# drv4.net
KiCad netlist of a schematic drawn in EAGLE
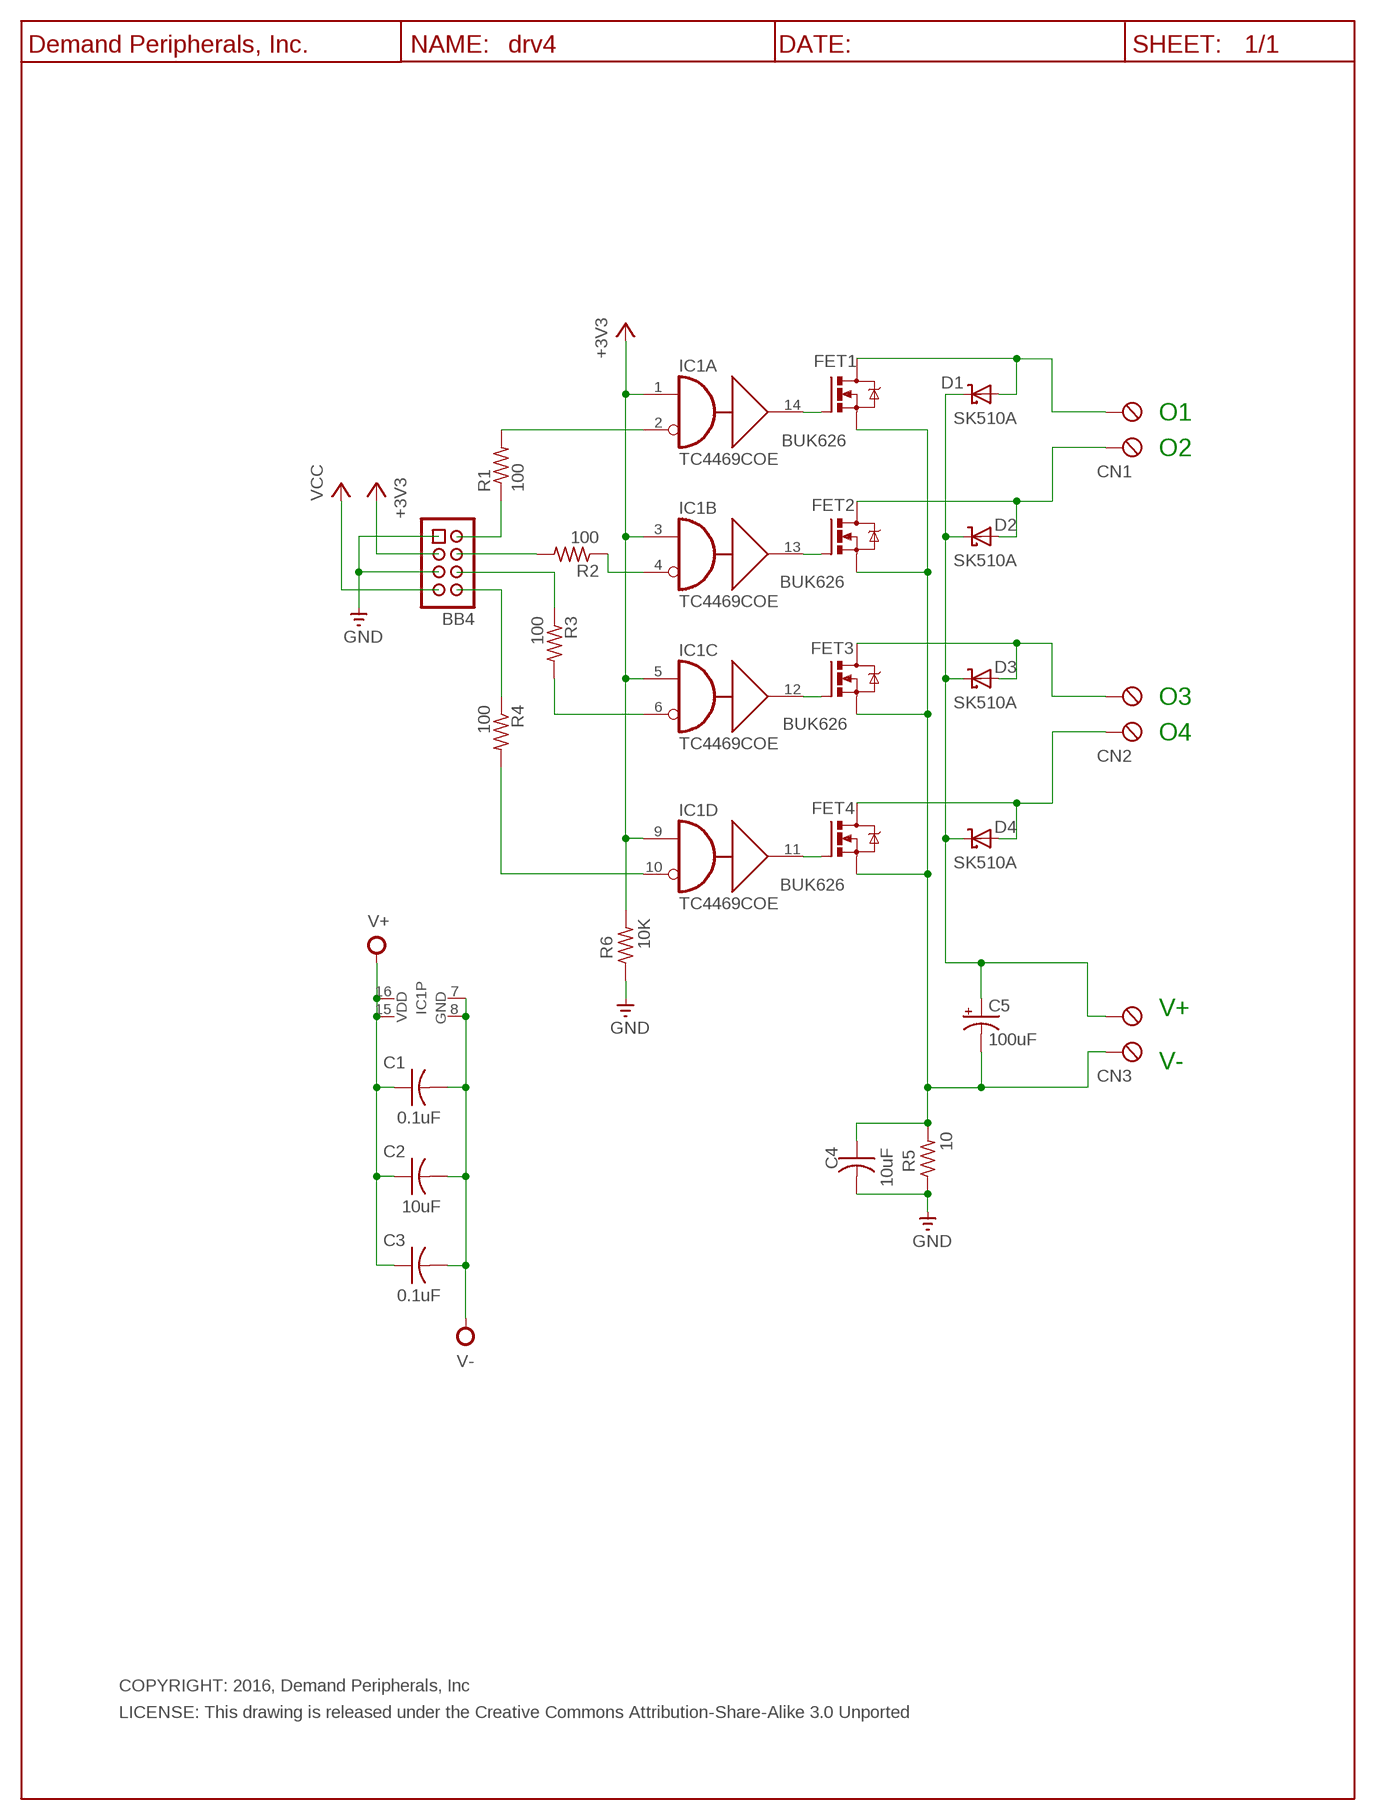
[diagram p0: schematic, sheet 1]

(export (version "E")
  (design (tool "Eeschema 10.0.6"))
  (components
    (comp (ref "BB4")
      (value "Keyed_Pin_Header_4x2(0.1\"x0.1\")")
      (footprint "eagle-import:HDR-4X2")
      (libsource (lib "eagle-import") (part "HDR-4X2-SHR"))
    )
    (comp (ref "C1")
      (value "0.1uF")
      (footprint "eagle-import:C0603")
      (libsource (lib "eagle-import") (part "C0.1UF_C0603"))
    )
    (comp (ref "C2")
      (value "10uF")
      (footprint "eagle-import:C0805")
      (libsource (lib "eagle-import") (part "C10UF35V_C0805"))
    )
    (comp (ref "C3")
      (value "0.1uF")
      (footprint "eagle-import:C0603")
      (libsource (lib "eagle-import") (part "C0.1UF_C0603"))
    )
    (comp (ref "C4")
      (value "10uF")
      (footprint "eagle-import:C0805")
      (libsource (lib "eagle-import") (part "C10UF35V_C0805"))
    )
    (comp (ref "C5")
      (value "100uF")
      (footprint "eagle-import:E3.5-8")
      (libsource (lib "eagle-import") (part "C100UF_E3.5-8"))
    )
    (comp (ref "CN1")
      (value "TBLK-5.08-X2")
      (footprint "eagle-import:TBLK-5.08-X2")
      (libsource (lib "eagle-import") (part "TBLK-5.08-X2"))
    )
    (comp (ref "CN2")
      (value "TBLK-5.08-X2")
      (footprint "eagle-import:TBLK-5.08-X2")
      (libsource (lib "eagle-import") (part "TBLK-5.08-X2"))
    )
    (comp (ref "CN3")
      (value "TBLK-5.08-X2")
      (footprint "eagle-import:TBLK-5.08-X2")
      (libsource (lib "eagle-import") (part "TBLK-5.08-X2"))
    )
    (comp (ref "D1")
      (value "SK510A")
      (footprint "eagle-import:SMA")
      (libsource (lib "eagle-import") (part "SK510A"))
    )
    (comp (ref "D2")
      (value "SK510A")
      (footprint "eagle-import:SMA")
      (libsource (lib "eagle-import") (part "SK510A"))
    )
    (comp (ref "D3")
      (value "SK510A")
      (footprint "eagle-import:SMA")
      (libsource (lib "eagle-import") (part "SK510A"))
    )
    (comp (ref "D4")
      (value "SK510A")
      (footprint "eagle-import:SMA")
      (libsource (lib "eagle-import") (part "SK510A"))
    )
    (comp (ref "FET1")
      (value "BUK626")
      (footprint "eagle-import:DPACK_TO-252")
      (libsource (lib "eagle-import") (part "BUK626"))
    )
    (comp (ref "FET2")
      (value "BUK626")
      (footprint "eagle-import:DPACK_TO-252")
      (libsource (lib "eagle-import") (part "BUK626"))
    )
    (comp (ref "FET3")
      (value "BUK626")
      (footprint "eagle-import:DPACK_TO-252")
      (libsource (lib "eagle-import") (part "BUK626"))
    )
    (comp (ref "FET4")
      (value "BUK626")
      (footprint "eagle-import:DPACK_TO-252")
      (libsource (lib "eagle-import") (part "BUK626"))
    )
    (comp (ref "IC1")
      (value "TC4469COE")
      (footprint "eagle-import:SO-16DW")
      (libsource (lib "eagle-import") (part "TC4469OESO-16DW"))
    )
    (comp (ref "R1")
      (value "100")
      (footprint "eagle-import:R0603")
      (libsource (lib "eagle-import") (part "R100_R0603"))
    )
    (comp (ref "R2")
      (value "100")
      (footprint "eagle-import:R0603")
      (libsource (lib "eagle-import") (part "R100_R0603"))
    )
    (comp (ref "R3")
      (value "100")
      (footprint "eagle-import:R0603")
      (libsource (lib "eagle-import") (part "R100_R0603"))
    )
    (comp (ref "R4")
      (value "100")
      (footprint "eagle-import:R0603")
      (libsource (lib "eagle-import") (part "R100_R0603"))
    )
    (comp (ref "R5")
      (value "10")
      (footprint "eagle-import:R0603")
      (libsource (lib "eagle-import") (part "R10_R0603"))
    )
    (comp (ref "R6")
      (value "10K")
      (footprint "eagle-import:R0603")
      (libsource (lib "eagle-import") (part "R10K_R0603"))
    )
    (comp (ref "U$1")
      (value "DP_FRAME_P")
      (footprint "eagle-import:P_FRAME")
      (libsource (lib "eagle-import") (part "DP_FRAME_P"))
    )
  )
  (nets
    (net (code "1") (name "+3V3") (class "Default")
      (node (ref "BB4") (pin "3") (pinfunction "3_3") (pintype "passive"))
      (node (ref "IC1") (pin "1") (pinfunction "A_1") (pintype "input"))
      (node (ref "IC1") (pin "3") (pinfunction "A_3") (pintype "input"))
      (node (ref "IC1") (pin "5") (pinfunction "A_5") (pintype "input"))
      (node (ref "IC1") (pin "9") (pinfunction "A_9") (pintype "input"))
      (node (ref "R6") (pin "2") (pinfunction "2_2") (pintype "passive"))
    )
    (net (code "2") (name "GND") (class "Default")
      (node (ref "BB4") (pin "1") (pinfunction "1_1") (pintype "passive"))
      (node (ref "BB4") (pin "5") (pinfunction "5_5") (pintype "passive"))
      (node (ref "C4") (pin "2") (pinfunction "2_2") (pintype "passive"))
      (node (ref "R5") (pin "1") (pinfunction "1_1") (pintype "passive"))
      (node (ref "R6") (pin "1") (pinfunction "1_1") (pintype "passive"))
    )
    (net (code "3") (name "Net-(BB4-Pad2)") (class "Default")
      (node (ref "BB4") (pin "2") (pinfunction "2_2") (pintype "passive"))
      (node (ref "R1") (pin "1") (pinfunction "1_1") (pintype "passive"))
    )
    (net (code "4") (name "Net-(BB4-Pad4)") (class "Default")
      (node (ref "BB4") (pin "4") (pinfunction "4_4") (pintype "passive"))
      (node (ref "R2") (pin "2") (pinfunction "2_2") (pintype "passive"))
    )
    (net (code "5") (name "Net-(BB4-Pad6)") (class "Default")
      (node (ref "BB4") (pin "6") (pinfunction "6_6") (pintype "passive"))
      (node (ref "R3") (pin "1") (pinfunction "1_1") (pintype "passive"))
    )
    (net (code "6") (name "Net-(BB4-Pad8)") (class "Default")
      (node (ref "BB4") (pin "8") (pinfunction "8_8") (pintype "passive"))
      (node (ref "R4") (pin "1") (pinfunction "1_1") (pintype "passive"))
    )
    (net (code "7") (name "Net-(CN1-KL)") (class "Default")
      (node (ref "CN1") (pin "1") (pinfunction "KL_1") (pintype "passive"))
      (node (ref "D2") (pin "A") (pinfunction "A_A") (pintype "passive"))
      (node (ref "FET2") (pin "4") (pinfunction "D_4") (pintype "passive"))
    )
    (net (code "8") (name "Net-(CN1-KL1)") (class "Default")
      (node (ref "CN1") (pin "2") (pinfunction "KL1_2") (pintype "passive"))
      (node (ref "D1") (pin "A") (pinfunction "A_A") (pintype "passive"))
      (node (ref "FET1") (pin "4") (pinfunction "D_4") (pintype "passive"))
    )
    (net (code "9") (name "Net-(CN2-KL)") (class "Default")
      (node (ref "CN2") (pin "1") (pinfunction "KL_1") (pintype "passive"))
      (node (ref "D4") (pin "A") (pinfunction "A_A") (pintype "passive"))
      (node (ref "FET4") (pin "4") (pinfunction "D_4") (pintype "passive"))
    )
    (net (code "10") (name "Net-(CN2-KL1)") (class "Default")
      (node (ref "CN2") (pin "2") (pinfunction "KL1_2") (pintype "passive"))
      (node (ref "D3") (pin "A") (pinfunction "A_A") (pintype "passive"))
      (node (ref "FET3") (pin "4") (pinfunction "D_4") (pintype "passive"))
    )
    (net (code "11") (name "Net-(FET1-G)") (class "Default")
      (node (ref "FET1") (pin "1") (pinfunction "G_1") (pintype "passive"))
      (node (ref "IC1") (pin "14") (pinfunction "Y_14") (pintype "output"))
    )
    (net (code "12") (name "Net-(FET2-G)") (class "Default")
      (node (ref "FET2") (pin "1") (pinfunction "G_1") (pintype "passive"))
      (node (ref "IC1") (pin "13") (pinfunction "Y_13") (pintype "output"))
    )
    (net (code "13") (name "Net-(FET3-G)") (class "Default")
      (node (ref "FET3") (pin "1") (pinfunction "G_1") (pintype "passive"))
      (node (ref "IC1") (pin "12") (pinfunction "Y_12") (pintype "output"))
    )
    (net (code "14") (name "Net-(FET4-G)") (class "Default")
      (node (ref "FET4") (pin "1") (pinfunction "G_1") (pintype "passive"))
      (node (ref "IC1") (pin "11") (pinfunction "Y_11") (pintype "output"))
    )
    (net (code "15") (name "Net-(IC1A-B)") (class "Default")
      (node (ref "IC1") (pin "2") (pinfunction "B_2") (pintype "input"))
      (node (ref "R1") (pin "2") (pinfunction "2_2") (pintype "passive"))
    )
    (net (code "16") (name "Net-(IC1B-B)") (class "Default")
      (node (ref "IC1") (pin "4") (pinfunction "B_4") (pintype "input"))
      (node (ref "R2") (pin "1") (pinfunction "1_1") (pintype "passive"))
    )
    (net (code "17") (name "Net-(IC1C-B)") (class "Default")
      (node (ref "IC1") (pin "6") (pinfunction "B_6") (pintype "input"))
      (node (ref "R3") (pin "2") (pinfunction "2_2") (pintype "passive"))
    )
    (net (code "18") (name "Net-(IC1D-B)") (class "Default")
      (node (ref "IC1") (pin "10") (pinfunction "B_10") (pintype "input"))
      (node (ref "R4") (pin "2") (pinfunction "2_2") (pintype "passive"))
    )
    (net (code "19") (name "V+") (class "Default")
      (node (ref "C1") (pin "1") (pinfunction "1_1") (pintype "passive"))
      (node (ref "C2") (pin "1") (pinfunction "1_1") (pintype "passive"))
      (node (ref "C3") (pin "1") (pinfunction "1_1") (pintype "passive"))
      (node (ref "C5") (pin "+") (pinfunction "+_+") (pintype "passive"))
      (node (ref "CN3") (pin "2") (pinfunction "KL1_2") (pintype "passive"))
      (node (ref "D1") (pin "C") (pinfunction "CC_C") (pintype "passive"))
      (node (ref "D2") (pin "C") (pinfunction "CC_C") (pintype "passive"))
      (node (ref "D3") (pin "C") (pinfunction "CC_C") (pintype "passive"))
      (node (ref "D4") (pin "C") (pinfunction "CC_C") (pintype "passive"))
      (node (ref "IC1") (pin "15") (pinfunction "VDD_15") (pintype "power_in"))
      (node (ref "IC1") (pin "16") (pinfunction "VDD_16") (pintype "power_in"))
    )
    (net (code "20") (name "V-") (class "Default")
      (node (ref "C1") (pin "2") (pinfunction "2_2") (pintype "passive"))
      (node (ref "C2") (pin "2") (pinfunction "2_2") (pintype "passive"))
      (node (ref "C3") (pin "2") (pinfunction "2_2") (pintype "passive"))
      (node (ref "C4") (pin "1") (pinfunction "1_1") (pintype "passive"))
      (node (ref "C5") (pin "-") (pinfunction "-_-") (pintype "passive"))
      (node (ref "CN3") (pin "1") (pinfunction "KL_1") (pintype "passive"))
      (node (ref "FET1") (pin "3") (pinfunction "S_3") (pintype "passive"))
      (node (ref "FET2") (pin "3") (pinfunction "S_3") (pintype "passive"))
      (node (ref "FET3") (pin "3") (pinfunction "S_3") (pintype "passive"))
      (node (ref "FET4") (pin "3") (pinfunction "S_3") (pintype "passive"))
      (node (ref "IC1") (pin "7") (pinfunction "GND_7") (pintype "power_in"))
      (node (ref "IC1") (pin "8") (pinfunction "GND_8") (pintype "power_in"))
      (node (ref "R5") (pin "2") (pinfunction "2_2") (pintype "passive"))
    )
    (net (code "21") (name "VCC") (class "Default")
      (node (ref "BB4") (pin "7") (pinfunction "7_7") (pintype "passive"))
    )
  )
)
